# ir_validator.net
KiCad netlist of a schematic drawn in EAGLE
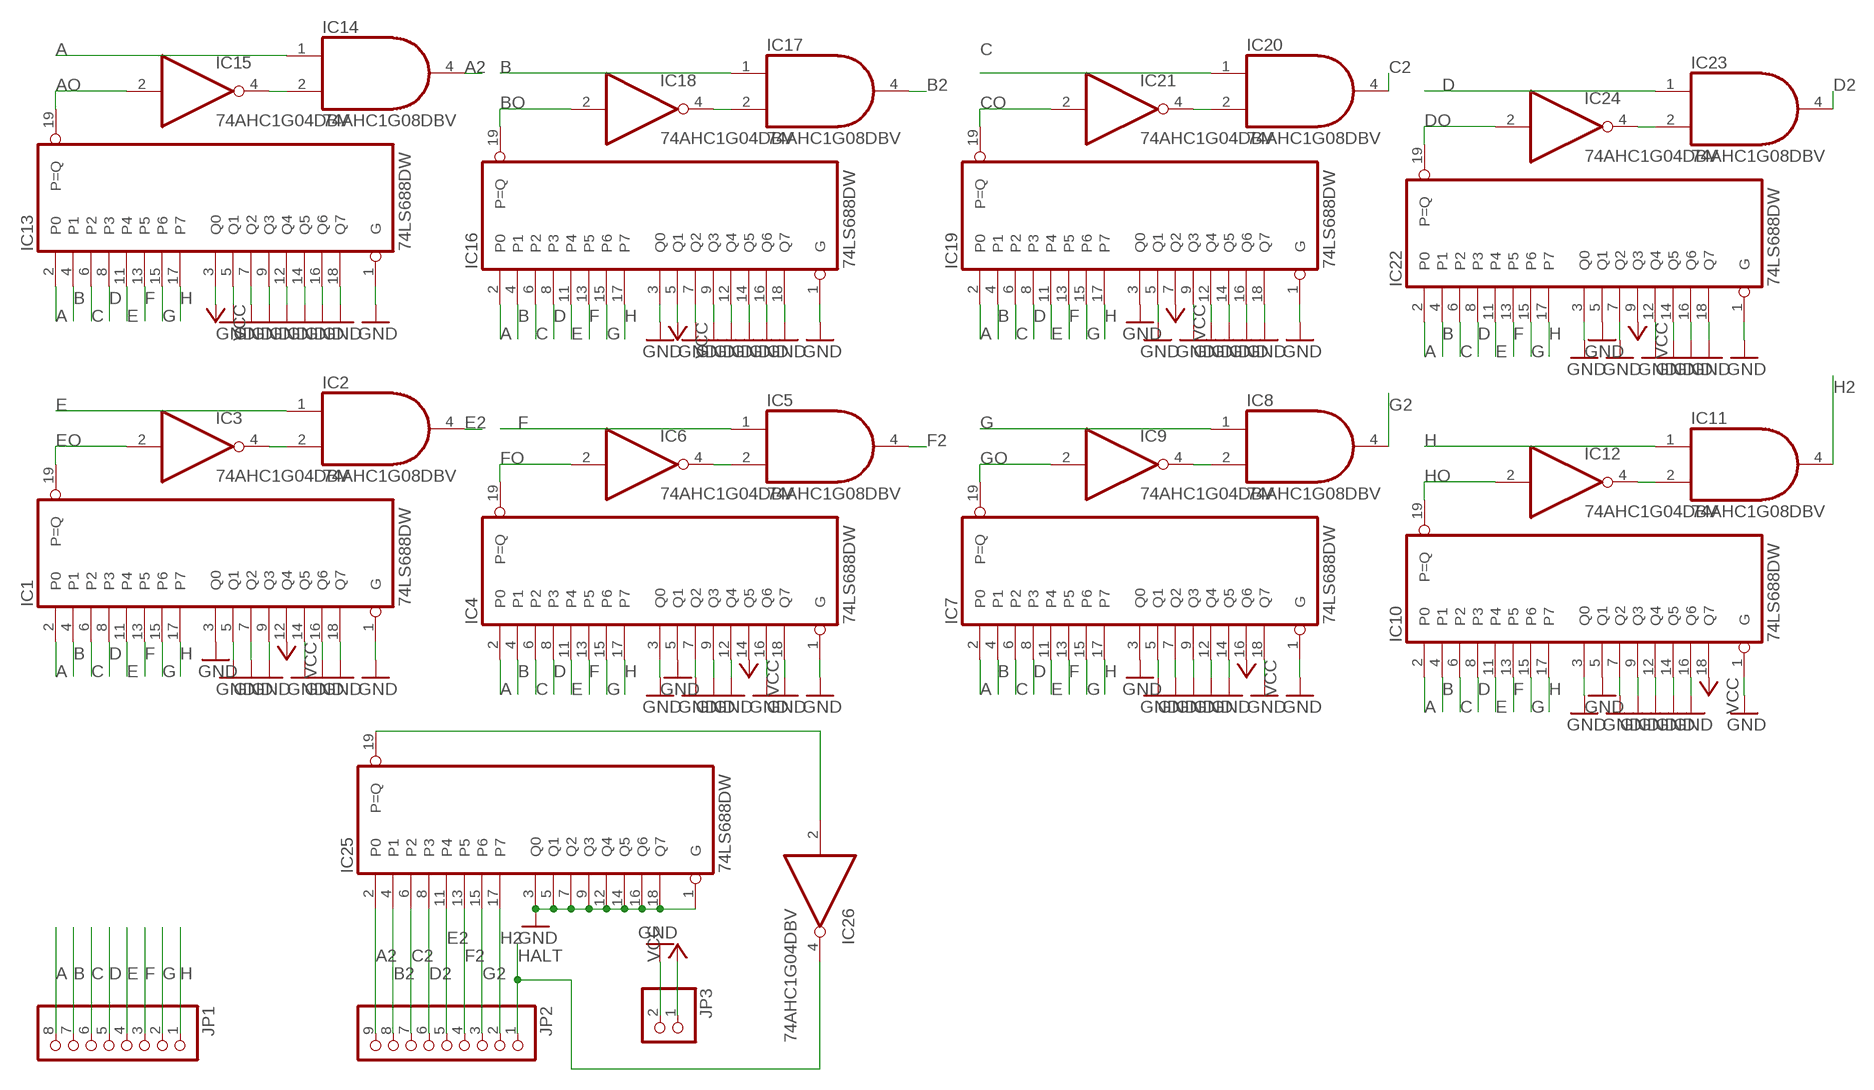
[diagram p0: schematic, sheet 1]

(export (version "E")
  (design (tool "Eeschema 10.0.6"))
  (components
    (comp (ref "IC1")
      (value "74LS688DW")
      (footprint "eagle-import:SO20W")
      (libsource (lib "eagle-import") (part "74688DWLS"))
    )
    (comp (ref "IC2")
      (value "74AHC1G08DBV")
      (footprint "eagle-import:SOT23-5")
      (libsource (lib "eagle-import") (part "741G08DBVAHC"))
    )
    (comp (ref "IC3")
      (value "74AHC1G04DBV")
      (footprint "eagle-import:SOT23-5")
      (libsource (lib "eagle-import") (part "741G04DBVAHC"))
    )
    (comp (ref "IC4")
      (value "74LS688DW")
      (footprint "eagle-import:SO20W")
      (libsource (lib "eagle-import") (part "74688DWLS"))
    )
    (comp (ref "IC5")
      (value "74AHC1G08DBV")
      (footprint "eagle-import:SOT23-5")
      (libsource (lib "eagle-import") (part "741G08DBVAHC"))
    )
    (comp (ref "IC6")
      (value "74AHC1G04DBV")
      (footprint "eagle-import:SOT23-5")
      (libsource (lib "eagle-import") (part "741G04DBVAHC"))
    )
    (comp (ref "IC7")
      (value "74LS688DW")
      (footprint "eagle-import:SO20W")
      (libsource (lib "eagle-import") (part "74688DWLS"))
    )
    (comp (ref "IC8")
      (value "74AHC1G08DBV")
      (footprint "eagle-import:SOT23-5")
      (libsource (lib "eagle-import") (part "741G08DBVAHC"))
    )
    (comp (ref "IC9")
      (value "74AHC1G04DBV")
      (footprint "eagle-import:SOT23-5")
      (libsource (lib "eagle-import") (part "741G04DBVAHC"))
    )
    (comp (ref "IC10")
      (value "74LS688DW")
      (footprint "eagle-import:SO20W")
      (libsource (lib "eagle-import") (part "74688DWLS"))
    )
    (comp (ref "IC11")
      (value "74AHC1G08DBV")
      (footprint "eagle-import:SOT23-5")
      (libsource (lib "eagle-import") (part "741G08DBVAHC"))
    )
    (comp (ref "IC12")
      (value "74AHC1G04DBV")
      (footprint "eagle-import:SOT23-5")
      (libsource (lib "eagle-import") (part "741G04DBVAHC"))
    )
    (comp (ref "IC13")
      (value "74LS688DW")
      (footprint "eagle-import:SO20W")
      (libsource (lib "eagle-import") (part "74688DWLS"))
    )
    (comp (ref "IC14")
      (value "74AHC1G08DBV")
      (footprint "eagle-import:SOT23-5")
      (libsource (lib "eagle-import") (part "741G08DBVAHC"))
    )
    (comp (ref "IC15")
      (value "74AHC1G04DBV")
      (footprint "eagle-import:SOT23-5")
      (libsource (lib "eagle-import") (part "741G04DBVAHC"))
    )
    (comp (ref "IC16")
      (value "74LS688DW")
      (footprint "eagle-import:SO20W")
      (libsource (lib "eagle-import") (part "74688DWLS"))
    )
    (comp (ref "IC17")
      (value "74AHC1G08DBV")
      (footprint "eagle-import:SOT23-5")
      (libsource (lib "eagle-import") (part "741G08DBVAHC"))
    )
    (comp (ref "IC18")
      (value "74AHC1G04DBV")
      (footprint "eagle-import:SOT23-5")
      (libsource (lib "eagle-import") (part "741G04DBVAHC"))
    )
    (comp (ref "IC19")
      (value "74LS688DW")
      (footprint "eagle-import:SO20W")
      (libsource (lib "eagle-import") (part "74688DWLS"))
    )
    (comp (ref "IC20")
      (value "74AHC1G08DBV")
      (footprint "eagle-import:SOT23-5")
      (libsource (lib "eagle-import") (part "741G08DBVAHC"))
    )
    (comp (ref "IC21")
      (value "74AHC1G04DBV")
      (footprint "eagle-import:SOT23-5")
      (libsource (lib "eagle-import") (part "741G04DBVAHC"))
    )
    (comp (ref "IC22")
      (value "74LS688DW")
      (footprint "eagle-import:SO20W")
      (libsource (lib "eagle-import") (part "74688DWLS"))
    )
    (comp (ref "IC23")
      (value "74AHC1G08DBV")
      (footprint "eagle-import:SOT23-5")
      (libsource (lib "eagle-import") (part "741G08DBVAHC"))
    )
    (comp (ref "IC24")
      (value "74AHC1G04DBV")
      (footprint "eagle-import:SOT23-5")
      (libsource (lib "eagle-import") (part "741G04DBVAHC"))
    )
    (comp (ref "IC25")
      (value "74LS688DW")
      (footprint "eagle-import:SO20W")
      (libsource (lib "eagle-import") (part "74688DWLS"))
    )
    (comp (ref "IC26")
      (value "74AHC1G04DBV")
      (footprint "eagle-import:SOT23-5")
      (libsource (lib "eagle-import") (part "741G04DBVAHC"))
    )
    (comp (ref "JP1")
      (value "PINHD-1X8")
      (footprint "eagle-import:1X08")
      (libsource (lib "eagle-import") (part "PINHD-1X8"))
    )
    (comp (ref "JP2")
      (value "PINHD-1X9")
      (footprint "eagle-import:1X09")
      (libsource (lib "eagle-import") (part "PINHD-1X9"))
    )
    (comp (ref "JP3")
      (value "PINHD-1X2")
      (footprint "eagle-import:1X02")
      (libsource (lib "eagle-import") (part "PINHD-1X2"))
    )
  )
  (nets
    (net (code "1") (name "/A") (class "Default")
      (node (ref "IC1") (pin "2") (pinfunction "P0_2") (pintype "input"))
      (node (ref "IC10") (pin "2") (pinfunction "P0_2") (pintype "input"))
      (node (ref "IC13") (pin "2") (pinfunction "P0_2") (pintype "input"))
      (node (ref "IC14") (pin "1") (pinfunction "I0_1") (pintype "input"))
      (node (ref "IC16") (pin "2") (pinfunction "P0_2") (pintype "input"))
      (node (ref "IC19") (pin "2") (pinfunction "P0_2") (pintype "input"))
      (node (ref "IC22") (pin "2") (pinfunction "P0_2") (pintype "input"))
      (node (ref "IC4") (pin "2") (pinfunction "P0_2") (pintype "input"))
      (node (ref "IC7") (pin "2") (pinfunction "P0_2") (pintype "input"))
      (node (ref "JP1") (pin "8") (pinfunction "8_8") (pintype "passive"))
    )
    (net (code "2") (name "/A2") (class "Default")
      (node (ref "IC14") (pin "4") (pinfunction "O_4") (pintype "output"))
      (node (ref "IC25") (pin "2") (pinfunction "P0_2") (pintype "input"))
      (node (ref "JP2") (pin "9") (pinfunction "9_9") (pintype "passive"))
    )
    (net (code "3") (name "/AO") (class "Default")
      (node (ref "IC13") (pin "19") (pinfunction "P=Q_19") (pintype "output"))
      (node (ref "IC15") (pin "2") (pinfunction "I_2") (pintype "input"))
    )
    (net (code "4") (name "/B") (class "Default")
      (node (ref "IC1") (pin "4") (pinfunction "P1_4") (pintype "input"))
      (node (ref "IC10") (pin "4") (pinfunction "P1_4") (pintype "input"))
      (node (ref "IC13") (pin "4") (pinfunction "P1_4") (pintype "input"))
      (node (ref "IC16") (pin "4") (pinfunction "P1_4") (pintype "input"))
      (node (ref "IC17") (pin "1") (pinfunction "I0_1") (pintype "input"))
      (node (ref "IC19") (pin "4") (pinfunction "P1_4") (pintype "input"))
      (node (ref "IC22") (pin "4") (pinfunction "P1_4") (pintype "input"))
      (node (ref "IC4") (pin "4") (pinfunction "P1_4") (pintype "input"))
      (node (ref "IC7") (pin "4") (pinfunction "P1_4") (pintype "input"))
      (node (ref "JP1") (pin "7") (pinfunction "7_7") (pintype "passive"))
    )
    (net (code "5") (name "/B2") (class "Default")
      (node (ref "IC17") (pin "4") (pinfunction "O_4") (pintype "output"))
      (node (ref "IC25") (pin "4") (pinfunction "P1_4") (pintype "input"))
      (node (ref "JP2") (pin "8") (pinfunction "8_8") (pintype "passive"))
    )
    (net (code "6") (name "/BO") (class "Default")
      (node (ref "IC16") (pin "19") (pinfunction "P=Q_19") (pintype "output"))
      (node (ref "IC18") (pin "2") (pinfunction "I_2") (pintype "input"))
    )
    (net (code "7") (name "/C") (class "Default")
      (node (ref "IC1") (pin "6") (pinfunction "P2_6") (pintype "input"))
      (node (ref "IC10") (pin "6") (pinfunction "P2_6") (pintype "input"))
      (node (ref "IC13") (pin "6") (pinfunction "P2_6") (pintype "input"))
      (node (ref "IC16") (pin "6") (pinfunction "P2_6") (pintype "input"))
      (node (ref "IC19") (pin "6") (pinfunction "P2_6") (pintype "input"))
      (node (ref "IC20") (pin "1") (pinfunction "I0_1") (pintype "input"))
      (node (ref "IC22") (pin "6") (pinfunction "P2_6") (pintype "input"))
      (node (ref "IC4") (pin "6") (pinfunction "P2_6") (pintype "input"))
      (node (ref "IC7") (pin "6") (pinfunction "P2_6") (pintype "input"))
      (node (ref "JP1") (pin "6") (pinfunction "6_6") (pintype "passive"))
    )
    (net (code "8") (name "/C2") (class "Default")
      (node (ref "IC20") (pin "4") (pinfunction "O_4") (pintype "output"))
      (node (ref "IC25") (pin "6") (pinfunction "P2_6") (pintype "input"))
      (node (ref "JP2") (pin "7") (pinfunction "7_7") (pintype "passive"))
    )
    (net (code "9") (name "/CO") (class "Default")
      (node (ref "IC19") (pin "19") (pinfunction "P=Q_19") (pintype "output"))
      (node (ref "IC21") (pin "2") (pinfunction "I_2") (pintype "input"))
    )
    (net (code "10") (name "/D") (class "Default")
      (node (ref "IC1") (pin "8") (pinfunction "P3_8") (pintype "input"))
      (node (ref "IC10") (pin "8") (pinfunction "P3_8") (pintype "input"))
      (node (ref "IC13") (pin "8") (pinfunction "P3_8") (pintype "input"))
      (node (ref "IC16") (pin "8") (pinfunction "P3_8") (pintype "input"))
      (node (ref "IC19") (pin "8") (pinfunction "P3_8") (pintype "input"))
      (node (ref "IC22") (pin "8") (pinfunction "P3_8") (pintype "input"))
      (node (ref "IC23") (pin "1") (pinfunction "I0_1") (pintype "input"))
      (node (ref "IC4") (pin "8") (pinfunction "P3_8") (pintype "input"))
      (node (ref "IC7") (pin "8") (pinfunction "P3_8") (pintype "input"))
      (node (ref "JP1") (pin "5") (pinfunction "5_5") (pintype "passive"))
    )
    (net (code "11") (name "/D2") (class "Default")
      (node (ref "IC23") (pin "4") (pinfunction "O_4") (pintype "output"))
      (node (ref "IC25") (pin "8") (pinfunction "P3_8") (pintype "input"))
      (node (ref "JP2") (pin "6") (pinfunction "6_6") (pintype "passive"))
    )
    (net (code "12") (name "/DO") (class "Default")
      (node (ref "IC22") (pin "19") (pinfunction "P=Q_19") (pintype "output"))
      (node (ref "IC24") (pin "2") (pinfunction "I_2") (pintype "input"))
    )
    (net (code "13") (name "/E") (class "Default")
      (node (ref "IC1") (pin "11") (pinfunction "P4_11") (pintype "input"))
      (node (ref "IC10") (pin "11") (pinfunction "P4_11") (pintype "input"))
      (node (ref "IC13") (pin "11") (pinfunction "P4_11") (pintype "input"))
      (node (ref "IC16") (pin "11") (pinfunction "P4_11") (pintype "input"))
      (node (ref "IC19") (pin "11") (pinfunction "P4_11") (pintype "input"))
      (node (ref "IC2") (pin "1") (pinfunction "I0_1") (pintype "input"))
      (node (ref "IC22") (pin "11") (pinfunction "P4_11") (pintype "input"))
      (node (ref "IC4") (pin "11") (pinfunction "P4_11") (pintype "input"))
      (node (ref "IC7") (pin "11") (pinfunction "P4_11") (pintype "input"))
      (node (ref "JP1") (pin "4") (pinfunction "4_4") (pintype "passive"))
    )
    (net (code "14") (name "/E2") (class "Default")
      (node (ref "IC2") (pin "4") (pinfunction "O_4") (pintype "output"))
      (node (ref "IC25") (pin "11") (pinfunction "P4_11") (pintype "input"))
      (node (ref "JP2") (pin "5") (pinfunction "5_5") (pintype "passive"))
    )
    (net (code "15") (name "/EO") (class "Default")
      (node (ref "IC1") (pin "19") (pinfunction "P=Q_19") (pintype "output"))
      (node (ref "IC3") (pin "2") (pinfunction "I_2") (pintype "input"))
    )
    (net (code "16") (name "/F") (class "Default")
      (node (ref "IC1") (pin "13") (pinfunction "P5_13") (pintype "input"))
      (node (ref "IC10") (pin "13") (pinfunction "P5_13") (pintype "input"))
      (node (ref "IC13") (pin "13") (pinfunction "P5_13") (pintype "input"))
      (node (ref "IC16") (pin "13") (pinfunction "P5_13") (pintype "input"))
      (node (ref "IC19") (pin "13") (pinfunction "P5_13") (pintype "input"))
      (node (ref "IC22") (pin "13") (pinfunction "P5_13") (pintype "input"))
      (node (ref "IC4") (pin "13") (pinfunction "P5_13") (pintype "input"))
      (node (ref "IC5") (pin "1") (pinfunction "I0_1") (pintype "input"))
      (node (ref "IC7") (pin "13") (pinfunction "P5_13") (pintype "input"))
      (node (ref "JP1") (pin "3") (pinfunction "3_3") (pintype "passive"))
    )
    (net (code "17") (name "/F2") (class "Default")
      (node (ref "IC25") (pin "13") (pinfunction "P5_13") (pintype "input"))
      (node (ref "IC5") (pin "4") (pinfunction "O_4") (pintype "output"))
      (node (ref "JP2") (pin "4") (pinfunction "4_4") (pintype "passive"))
    )
    (net (code "18") (name "/FO") (class "Default")
      (node (ref "IC4") (pin "19") (pinfunction "P=Q_19") (pintype "output"))
      (node (ref "IC6") (pin "2") (pinfunction "I_2") (pintype "input"))
    )
    (net (code "19") (name "/G") (class "Default")
      (node (ref "IC1") (pin "15") (pinfunction "P6_15") (pintype "input"))
      (node (ref "IC10") (pin "15") (pinfunction "P6_15") (pintype "input"))
      (node (ref "IC13") (pin "15") (pinfunction "P6_15") (pintype "input"))
      (node (ref "IC16") (pin "15") (pinfunction "P6_15") (pintype "input"))
      (node (ref "IC19") (pin "15") (pinfunction "P6_15") (pintype "input"))
      (node (ref "IC22") (pin "15") (pinfunction "P6_15") (pintype "input"))
      (node (ref "IC4") (pin "15") (pinfunction "P6_15") (pintype "input"))
      (node (ref "IC7") (pin "15") (pinfunction "P6_15") (pintype "input"))
      (node (ref "IC8") (pin "1") (pinfunction "I0_1") (pintype "input"))
      (node (ref "JP1") (pin "2") (pinfunction "2_2") (pintype "passive"))
    )
    (net (code "20") (name "/G2") (class "Default")
      (node (ref "IC25") (pin "15") (pinfunction "P6_15") (pintype "input"))
      (node (ref "IC8") (pin "4") (pinfunction "O_4") (pintype "output"))
      (node (ref "JP2") (pin "3") (pinfunction "3_3") (pintype "passive"))
    )
    (net (code "21") (name "/GO") (class "Default")
      (node (ref "IC7") (pin "19") (pinfunction "P=Q_19") (pintype "output"))
      (node (ref "IC9") (pin "2") (pinfunction "I_2") (pintype "input"))
    )
    (net (code "22") (name "/H") (class "Default")
      (node (ref "IC1") (pin "17") (pinfunction "P7_17") (pintype "input"))
      (node (ref "IC10") (pin "17") (pinfunction "P7_17") (pintype "input"))
      (node (ref "IC11") (pin "1") (pinfunction "I0_1") (pintype "input"))
      (node (ref "IC13") (pin "17") (pinfunction "P7_17") (pintype "input"))
      (node (ref "IC16") (pin "17") (pinfunction "P7_17") (pintype "input"))
      (node (ref "IC19") (pin "17") (pinfunction "P7_17") (pintype "input"))
      (node (ref "IC22") (pin "17") (pinfunction "P7_17") (pintype "input"))
      (node (ref "IC4") (pin "17") (pinfunction "P7_17") (pintype "input"))
      (node (ref "IC7") (pin "17") (pinfunction "P7_17") (pintype "input"))
      (node (ref "JP1") (pin "1") (pinfunction "1_1") (pintype "passive"))
    )
    (net (code "23") (name "/H2") (class "Default")
      (node (ref "IC11") (pin "4") (pinfunction "O_4") (pintype "output"))
      (node (ref "IC25") (pin "17") (pinfunction "P7_17") (pintype "input"))
      (node (ref "JP2") (pin "2") (pinfunction "2_2") (pintype "passive"))
    )
    (net (code "24") (name "/HALT") (class "Default")
      (node (ref "IC26") (pin "4") (pinfunction "O_4") (pintype "output"))
      (node (ref "JP2") (pin "1") (pinfunction "1_1") (pintype "passive"))
    )
    (net (code "25") (name "/HO") (class "Default")
      (node (ref "IC10") (pin "19") (pinfunction "P=Q_19") (pintype "output"))
      (node (ref "IC12") (pin "2") (pinfunction "I_2") (pintype "input"))
    )
    (net (code "26") (name "GND") (class "Default")
      (node (ref "IC1") (pin "1") (pinfunction "G_1") (pintype "input"))
      (node (ref "IC1") (pin "14") (pinfunction "Q5_14") (pintype "input"))
      (node (ref "IC1") (pin "16") (pinfunction "Q6_16") (pintype "input"))
      (node (ref "IC1") (pin "18") (pinfunction "Q7_18") (pintype "input"))
      (node (ref "IC1") (pin "3") (pinfunction "Q0_3") (pintype "input"))
      (node (ref "IC1") (pin "5") (pinfunction "Q1_5") (pintype "input"))
      (node (ref "IC1") (pin "7") (pinfunction "Q2_7") (pintype "input"))
      (node (ref "IC1") (pin "9") (pinfunction "Q3_9") (pintype "input"))
      (node (ref "IC10") (pin "1") (pinfunction "G_1") (pintype "input"))
      (node (ref "IC10") (pin "12") (pinfunction "Q4_12") (pintype "input"))
      (node (ref "IC10") (pin "14") (pinfunction "Q5_14") (pintype "input"))
      (node (ref "IC10") (pin "16") (pinfunction "Q6_16") (pintype "input"))
      (node (ref "IC10") (pin "3") (pinfunction "Q0_3") (pintype "input"))
      (node (ref "IC10") (pin "5") (pinfunction "Q1_5") (pintype "input"))
      (node (ref "IC10") (pin "7") (pinfunction "Q2_7") (pintype "input"))
      (node (ref "IC10") (pin "9") (pinfunction "Q3_9") (pintype "input"))
      (node (ref "IC13") (pin "1") (pinfunction "G_1") (pintype "input"))
      (node (ref "IC13") (pin "12") (pinfunction "Q4_12") (pintype "input"))
      (node (ref "IC13") (pin "14") (pinfunction "Q5_14") (pintype "input"))
      (node (ref "IC13") (pin "16") (pinfunction "Q6_16") (pintype "input"))
      (node (ref "IC13") (pin "18") (pinfunction "Q7_18") (pintype "input"))
      (node (ref "IC13") (pin "5") (pinfunction "Q1_5") (pintype "input"))
      (node (ref "IC13") (pin "7") (pinfunction "Q2_7") (pintype "input"))
      (node (ref "IC13") (pin "9") (pinfunction "Q3_9") (pintype "input"))
      (node (ref "IC16") (pin "1") (pinfunction "G_1") (pintype "input"))
      (node (ref "IC16") (pin "12") (pinfunction "Q4_12") (pintype "input"))
      (node (ref "IC16") (pin "14") (pinfunction "Q5_14") (pintype "input"))
      (node (ref "IC16") (pin "16") (pinfunction "Q6_16") (pintype "input"))
      (node (ref "IC16") (pin "18") (pinfunction "Q7_18") (pintype "input"))
      (node (ref "IC16") (pin "3") (pinfunction "Q0_3") (pintype "input"))
      (node (ref "IC16") (pin "7") (pinfunction "Q2_7") (pintype "input"))
      (node (ref "IC16") (pin "9") (pinfunction "Q3_9") (pintype "input"))
      (node (ref "IC19") (pin "1") (pinfunction "G_1") (pintype "input"))
      (node (ref "IC19") (pin "12") (pinfunction "Q4_12") (pintype "input"))
      (node (ref "IC19") (pin "14") (pinfunction "Q5_14") (pintype "input"))
      (node (ref "IC19") (pin "16") (pinfunction "Q6_16") (pintype "input"))
      (node (ref "IC19") (pin "18") (pinfunction "Q7_18") (pintype "input"))
      (node (ref "IC19") (pin "3") (pinfunction "Q0_3") (pintype "input"))
      (node (ref "IC19") (pin "5") (pinfunction "Q1_5") (pintype "input"))
      (node (ref "IC19") (pin "9") (pinfunction "Q3_9") (pintype "input"))
      (node (ref "IC22") (pin "1") (pinfunction "G_1") (pintype "input"))
      (node (ref "IC22") (pin "12") (pinfunction "Q4_12") (pintype "input"))
      (node (ref "IC22") (pin "14") (pinfunction "Q5_14") (pintype "input"))
      (node (ref "IC22") (pin "16") (pinfunction "Q6_16") (pintype "input"))
      (node (ref "IC22") (pin "18") (pinfunction "Q7_18") (pintype "input"))
      (node (ref "IC22") (pin "3") (pinfunction "Q0_3") (pintype "input"))
      (node (ref "IC22") (pin "5") (pinfunction "Q1_5") (pintype "input"))
      (node (ref "IC22") (pin "7") (pinfunction "Q2_7") (pintype "input"))
      (node (ref "IC25") (pin "1") (pinfunction "G_1") (pintype "input"))
      (node (ref "IC25") (pin "12") (pinfunction "Q4_12") (pintype "input"))
      (node (ref "IC25") (pin "14") (pinfunction "Q5_14") (pintype "input"))
      (node (ref "IC25") (pin "16") (pinfunction "Q6_16") (pintype "input"))
      (node (ref "IC25") (pin "18") (pinfunction "Q7_18") (pintype "input"))
      (node (ref "IC25") (pin "3") (pinfunction "Q0_3") (pintype "input"))
      (node (ref "IC25") (pin "5") (pinfunction "Q1_5") (pintype "input"))
      (node (ref "IC25") (pin "7") (pinfunction "Q2_7") (pintype "input"))
      (node (ref "IC25") (pin "9") (pinfunction "Q3_9") (pintype "input"))
      (node (ref "IC4") (pin "1") (pinfunction "G_1") (pintype "input"))
      (node (ref "IC4") (pin "12") (pinfunction "Q4_12") (pintype "input"))
      (node (ref "IC4") (pin "16") (pinfunction "Q6_16") (pintype "input"))
      (node (ref "IC4") (pin "18") (pinfunction "Q7_18") (pintype "input"))
      (node (ref "IC4") (pin "3") (pinfunction "Q0_3") (pintype "input"))
      (node (ref "IC4") (pin "5") (pinfunction "Q1_5") (pintype "input"))
      (node (ref "IC4") (pin "7") (pinfunction "Q2_7") (pintype "input"))
      (node (ref "IC4") (pin "9") (pinfunction "Q3_9") (pintype "input"))
      (node (ref "IC7") (pin "1") (pinfunction "G_1") (pintype "input"))
      (node (ref "IC7") (pin "12") (pinfunction "Q4_12") (pintype "input"))
      (node (ref "IC7") (pin "14") (pinfunction "Q5_14") (pintype "input"))
      (node (ref "IC7") (pin "18") (pinfunction "Q7_18") (pintype "input"))
      (node (ref "IC7") (pin "3") (pinfunction "Q0_3") (pintype "input"))
      (node (ref "IC7") (pin "5") (pinfunction "Q1_5") (pintype "input"))
      (node (ref "IC7") (pin "7") (pinfunction "Q2_7") (pintype "input"))
      (node (ref "IC7") (pin "9") (pinfunction "Q3_9") (pintype "input"))
      (node (ref "JP3") (pin "2") (pinfunction "2_2") (pintype "passive"))
    )
    (net (code "27") (name "Net-(IC2A-I1)") (class "Default")
      (node (ref "IC2") (pin "2") (pinfunction "I1_2") (pintype "input"))
      (node (ref "IC3") (pin "4") (pinfunction "O_4") (pintype "output"))
    )
    (net (code "28") (name "Net-(IC5A-I1)") (class "Default")
      (node (ref "IC5") (pin "2") (pinfunction "I1_2") (pintype "input"))
      (node (ref "IC6") (pin "4") (pinfunction "O_4") (pintype "output"))
    )
    (net (code "29") (name "Net-(IC8A-I1)") (class "Default")
      (node (ref "IC8") (pin "2") (pinfunction "I1_2") (pintype "input"))
      (node (ref "IC9") (pin "4") (pinfunction "O_4") (pintype "output"))
    )
    (net (code "30") (name "Net-(IC11A-I1)") (class "Default")
      (node (ref "IC11") (pin "2") (pinfunction "I1_2") (pintype "input"))
      (node (ref "IC12") (pin "4") (pinfunction "O_4") (pintype "output"))
    )
    (net (code "31") (name "Net-(IC14A-I1)") (class "Default")
      (node (ref "IC14") (pin "2") (pinfunction "I1_2") (pintype "input"))
      (node (ref "IC15") (pin "4") (pinfunction "O_4") (pintype "output"))
    )
    (net (code "32") (name "Net-(IC17A-I1)") (class "Default")
      (node (ref "IC17") (pin "2") (pinfunction "I1_2") (pintype "input"))
      (node (ref "IC18") (pin "4") (pinfunction "O_4") (pintype "output"))
    )
    (net (code "33") (name "Net-(IC20A-I1)") (class "Default")
      (node (ref "IC20") (pin "2") (pinfunction "I1_2") (pintype "input"))
      (node (ref "IC21") (pin "4") (pinfunction "O_4") (pintype "output"))
    )
    (net (code "34") (name "Net-(IC23A-I1)") (class "Default")
      (node (ref "IC23") (pin "2") (pinfunction "I1_2") (pintype "input"))
      (node (ref "IC24") (pin "4") (pinfunction "O_4") (pintype "output"))
    )
    (net (code "35") (name "Net-(IC25A-P=Q)") (class "Default")
      (node (ref "IC25") (pin "19") (pinfunction "P=Q_19") (pintype "output"))
      (node (ref "IC26") (pin "2") (pinfunction "I_2") (pintype "input"))
    )
    (net (code "36") (name "VCC") (class "Default")
      (node (ref "IC1") (pin "12") (pinfunction "Q4_12") (pintype "input"))
      (node (ref "IC10") (pin "18") (pinfunction "Q7_18") (pintype "input"))
      (node (ref "IC13") (pin "3") (pinfunction "Q0_3") (pintype "input"))
      (node (ref "IC16") (pin "5") (pinfunction "Q1_5") (pintype "input"))
      (node (ref "IC19") (pin "7") (pinfunction "Q2_7") (pintype "input"))
      (node (ref "IC22") (pin "9") (pinfunction "Q3_9") (pintype "input"))
      (node (ref "IC4") (pin "14") (pinfunction "Q5_14") (pintype "input"))
      (node (ref "IC7") (pin "16") (pinfunction "Q6_16") (pintype "input"))
      (node (ref "JP3") (pin "1") (pinfunction "1_1") (pintype "passive"))
    )
  )
)
